# MicroMultimeter_EXP_Sch.net
KiCad netlist of a schematic drawn in Altium Designer
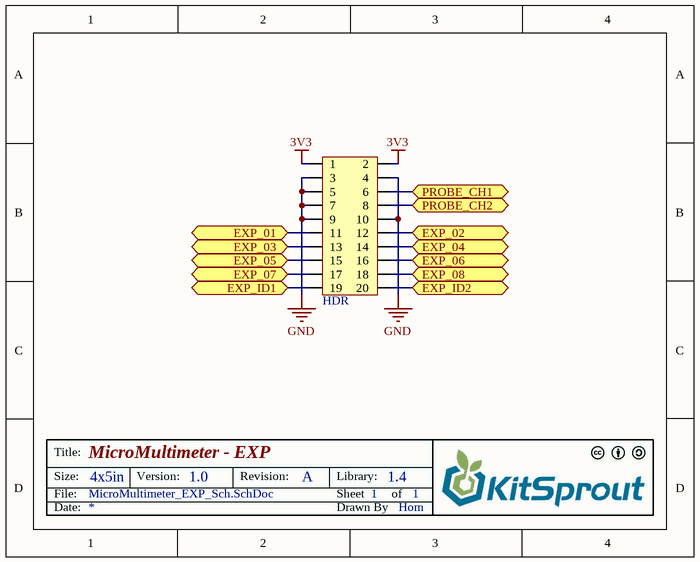
[diagram p0: MicroMultimeter_EXP_Sch.SchDoc]

(export (version "E")
  (design (tool "Eeschema 10.0.6"))
  (components
    (comp (ref "HDR")
      (value "HDR2x10_2.54")
      (footprint "PCB_ConnectorHDR:HDR2X10_2.54_180HF")
      (description "Header")
      (libsource (lib "SCH_ConnectorHDR") (part "HDR2x10_2.54"))
    )
  )
  (nets
    (net (code "1") (name "/EXP_01") (class "Default")
      (node (ref "HDR") (pin "11") (pinfunction "11_11") (pintype "passive"))
    )
    (net (code "2") (name "/EXP_02") (class "Default")
      (node (ref "HDR") (pin "12") (pinfunction "12_12") (pintype "passive"))
    )
    (net (code "3") (name "/EXP_03") (class "Default")
      (node (ref "HDR") (pin "13") (pinfunction "13_13") (pintype "passive"))
    )
    (net (code "4") (name "/EXP_04") (class "Default")
      (node (ref "HDR") (pin "14") (pinfunction "14_14") (pintype "passive"))
    )
    (net (code "5") (name "/EXP_05") (class "Default")
      (node (ref "HDR") (pin "15") (pinfunction "15_15") (pintype "passive"))
    )
    (net (code "6") (name "/EXP_06") (class "Default")
      (node (ref "HDR") (pin "16") (pinfunction "16_16") (pintype "passive"))
    )
    (net (code "7") (name "/EXP_07") (class "Default")
      (node (ref "HDR") (pin "17") (pinfunction "17_17") (pintype "passive"))
    )
    (net (code "8") (name "/EXP_08") (class "Default")
      (node (ref "HDR") (pin "18") (pinfunction "18_18") (pintype "passive"))
    )
    (net (code "9") (name "/EXP_ID1") (class "Default")
      (node (ref "HDR") (pin "19") (pinfunction "19_19") (pintype "passive"))
    )
    (net (code "10") (name "/EXP_ID2") (class "Default")
      (node (ref "HDR") (pin "20") (pinfunction "20_20") (pintype "passive"))
    )
    (net (code "11") (name "/PROBE_CH1") (class "Default")
      (node (ref "HDR") (pin "6") (pinfunction "6_6") (pintype "passive"))
    )
    (net (code "12") (name "/PROBE_CH2") (class "Default")
      (node (ref "HDR") (pin "8") (pinfunction "8_8") (pintype "passive"))
    )
    (net (code "13") (name "3V3") (class "Default")
      (node (ref "HDR") (pin "1") (pinfunction "1_1") (pintype "passive"))
      (node (ref "HDR") (pin "2") (pinfunction "2_2") (pintype "passive"))
    )
    (net (code "14") (name "GND") (class "Default")
      (node (ref "HDR") (pin "10") (pinfunction "10_10") (pintype "passive"))
      (node (ref "HDR") (pin "3") (pinfunction "3_3") (pintype "passive"))
      (node (ref "HDR") (pin "4") (pinfunction "4_4") (pintype "passive"))
      (node (ref "HDR") (pin "5") (pinfunction "5_5") (pintype "passive"))
      (node (ref "HDR") (pin "7") (pinfunction "7_7") (pintype "passive"))
      (node (ref "HDR") (pin "9") (pinfunction "9_9") (pintype "passive"))
    )
  )
)
